# CycleOpsPro300toANTPlus_V2_0.net
KiCad netlist of a schematic drawn in EAGLE
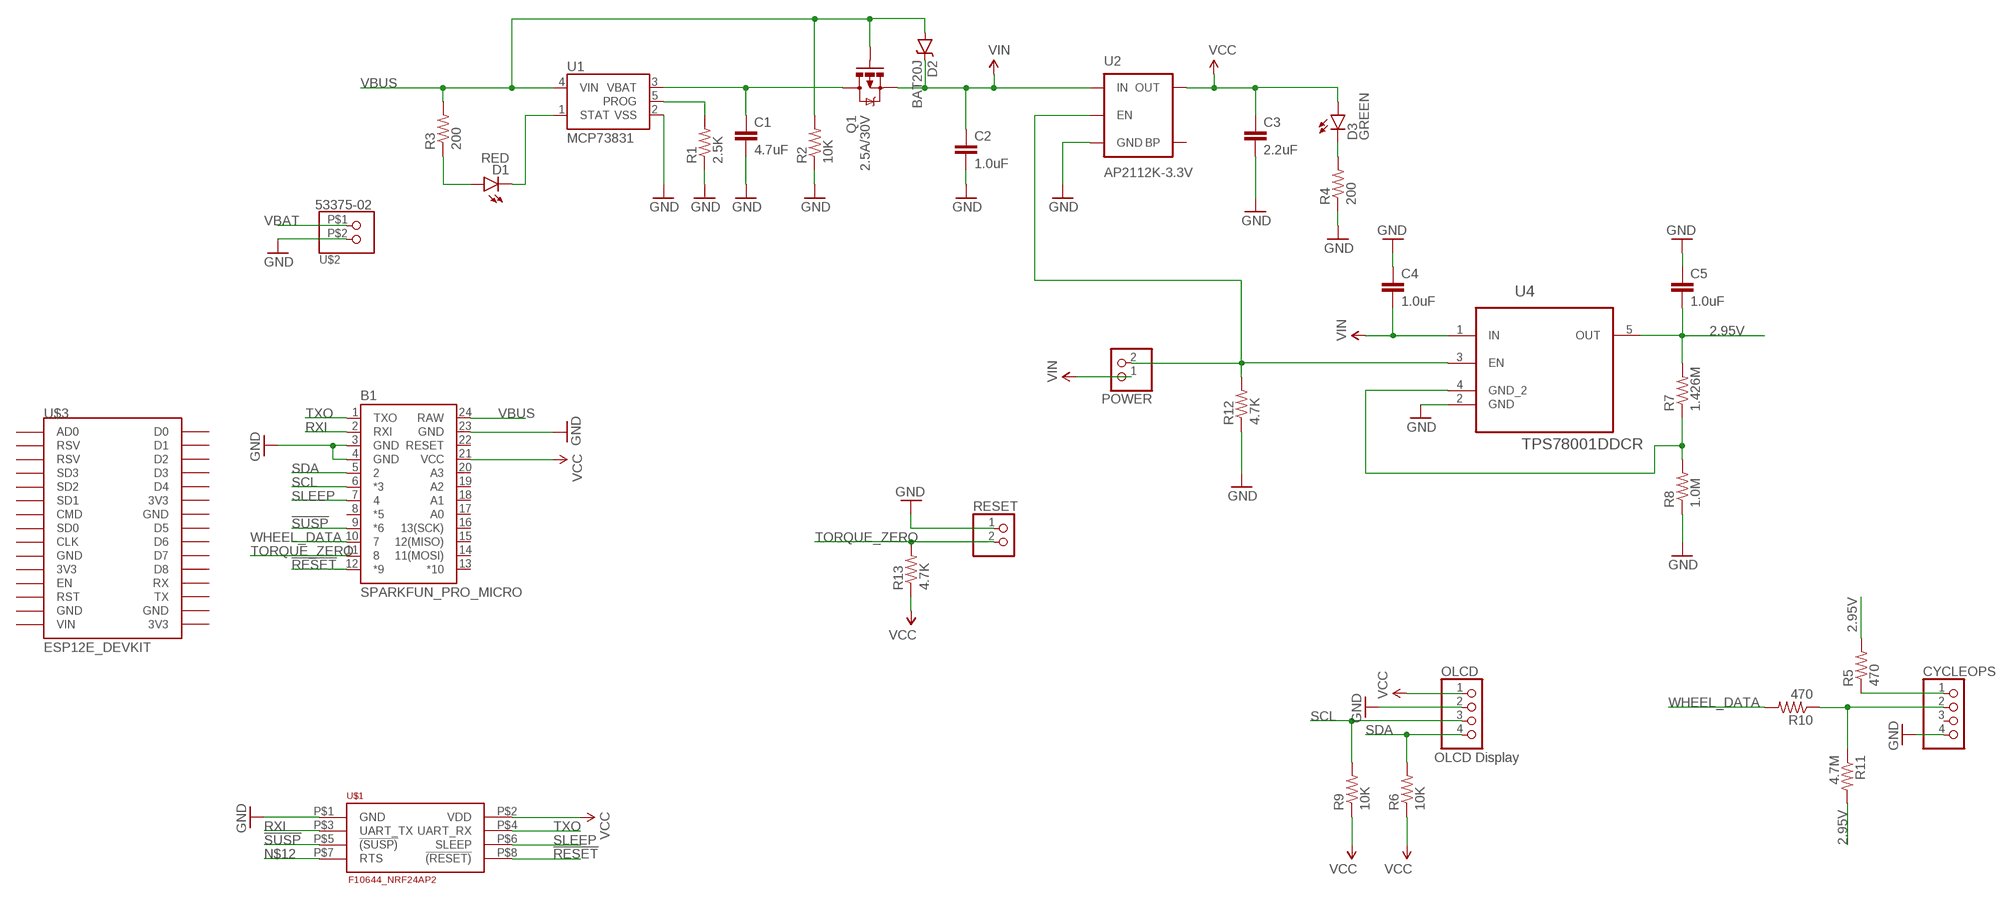
[diagram p0: schematic, sheet 1]

(export (version "E")
  (design (tool "Eeschema 10.0.6"))
  (components
    (comp (ref "B1")
      (value "SPARKFUN_PRO_MICRO")
      (footprint "eagle-import:SPARKFUN_PRO_MICRO")
      (libsource (lib "eagle-import") (part "SPARKFUN_PRO_MICRO"))
    )
    (comp (ref "C1")
      (value "4.7uF")
      (footprint "eagle-import:0603-CAP")
      (libsource (lib "eagle-import") (part "CAP0603-CAP"))
    )
    (comp (ref "C2")
      (value "1.0uF")
      (footprint "eagle-import:0603-CAP")
      (libsource (lib "eagle-import") (part "CAP0603-CAP"))
    )
    (comp (ref "C3")
      (value "2.2uF")
      (footprint "eagle-import:0603-CAP")
      (libsource (lib "eagle-import") (part "CAP0603-CAP"))
    )
    (comp (ref "C4")
      (value "1.0uF")
      (footprint "eagle-import:0603-CAP")
      (libsource (lib "eagle-import") (part "CAP0603-CAP"))
    )
    (comp (ref "C5")
      (value "1.0uF")
      (footprint "eagle-import:0603-CAP")
      (libsource (lib "eagle-import") (part "CAP0603-CAP"))
    )
    (comp (ref "CYCLEOPS")
      (value "PINHD-1X4")
      (footprint "eagle-import:1X04")
      (libsource (lib "eagle-import") (part "PINHD-1X4"))
    )
    (comp (ref "D1")
      (value "RED")
      (footprint "eagle-import:LED-0603")
      (libsource (lib "eagle-import") (part "LED0603"))
    )
    (comp (ref "D2")
      (value "BAT20J")
      (footprint "eagle-import:SOD-323")
      (libsource (lib "eagle-import") (part "DIODE-SCHOTTKY-BAT20J"))
    )
    (comp (ref "D3")
      (value "GREEN")
      (footprint "eagle-import:LED-0603")
      (libsource (lib "eagle-import") (part "LED0603"))
    )
    (comp (ref "OLCD")
      (value "PINHD-1X4")
      (footprint "eagle-import:1X04")
      (libsource (lib "eagle-import") (part "PINHD-1X4"))
    )
    (comp (ref "POWER")
      (value "PINHD-1X2")
      (footprint "eagle-import:1X02")
      (libsource (lib "eagle-import") (part "PINHD-1X2"))
    )
    (comp (ref "Q1")
      (value "2.5A/30V")
      (footprint "eagle-import:SOT23-3")
      (libsource (lib "eagle-import") (part "MOSFET-PCHANNELDMG2307L"))
    )
    (comp (ref "R1")
      (value "2.5K")
      (footprint "eagle-import:0603-RES")
      (libsource (lib "eagle-import") (part "RESISTOR0603-RES"))
    )
    (comp (ref "R2")
      (value "10K")
      (footprint "eagle-import:0603-RES")
      (libsource (lib "eagle-import") (part "RESISTOR0603-RES"))
    )
    (comp (ref "R3")
      (value "200")
      (footprint "eagle-import:0603-RES")
      (libsource (lib "eagle-import") (part "RESISTOR0603-RES"))
    )
    (comp (ref "R4")
      (value "200")
      (footprint "eagle-import:0603-RES")
      (libsource (lib "eagle-import") (part "RESISTOR0603-RES"))
    )
    (comp (ref "R5")
      (value "470")
      (footprint "eagle-import:0603-RES")
      (libsource (lib "eagle-import") (part "RESISTOR0603-RES"))
    )
    (comp (ref "R6")
      (value "10K")
      (footprint "eagle-import:0603-RES")
      (libsource (lib "eagle-import") (part "RESISTOR0603-RES"))
    )
    (comp (ref "R7")
      (value "1.426M")
      (footprint "eagle-import:0603-RES")
      (libsource (lib "eagle-import") (part "RESISTOR0603-RES"))
    )
    (comp (ref "R8")
      (value "1.0M")
      (footprint "eagle-import:0603-RES")
      (libsource (lib "eagle-import") (part "RESISTOR0603-RES"))
    )
    (comp (ref "R9")
      (value "10K")
      (footprint "eagle-import:0603-RES")
      (libsource (lib "eagle-import") (part "RESISTOR0603-RES"))
    )
    (comp (ref "R10")
      (value "470")
      (footprint "eagle-import:0603-RES")
      (libsource (lib "eagle-import") (part "RESISTOR0603-RES"))
    )
    (comp (ref "R11")
      (value "4.7M")
      (footprint "eagle-import:0603-RES")
      (libsource (lib "eagle-import") (part "RESISTOR0603-RES"))
    )
    (comp (ref "R12")
      (value "4.7K")
      (footprint "eagle-import:0603-RES")
      (libsource (lib "eagle-import") (part "RESISTOR0603-RES"))
    )
    (comp (ref "R13")
      (value "4.7K")
      (footprint "eagle-import:0603-RES")
      (libsource (lib "eagle-import") (part "RESISTOR0603-RES"))
    )
    (comp (ref "RESET")
      (value "PINHD-1X2")
      (footprint "eagle-import:1X02")
      (libsource (lib "eagle-import") (part "PINHD-1X2"))
    )
    (comp (ref "U$1")
      (value "F10644_NRF24AP2")
      (footprint "eagle-import:F10644_NRF24AP2")
      (libsource (lib "eagle-import") (part "F10644_NRF24AP2"))
    )
    (comp (ref "U$2")
      (value "53375-02")
      (footprint "eagle-import:53375-02")
      (libsource (lib "eagle-import") (part "53375-02"))
    )
    (comp (ref "U$3")
      (value "ESP12E_DEVKIT")
      (footprint "eagle-import:ESP12E_DEVKIT")
      (libsource (lib "eagle-import") (part "ESP12E_DEVKIT"))
    )
    (comp (ref "U1")
      (value "MCP73831")
      (footprint "eagle-import:SOT23-5")
      (libsource (lib "eagle-import") (part "MCP73831"))
    )
    (comp (ref "U2")
      (value "AP2112K-3.3V")
      (footprint "eagle-import:SOT23-5")
      (libsource (lib "eagle-import") (part "V_REG_LDOSMD"))
    )
    (comp (ref "U4")
      (value "TPS78001DDCR")
      (footprint "eagle-import:SOT95P280X110-5N")
      (fields (field (name "MPN") "TPS78223DDCR"))
      (libsource (lib "eagle-import") (part "TPS78223DDCR"))
    )
  )
  (nets
    (net (code "1") (name "/2.95V") (class "Default")
      (node (ref "C5") (pin "2") (pinfunction "2_2") (pintype "passive"))
      (node (ref "R11") (pin "2") (pinfunction "2_2") (pintype "passive"))
      (node (ref "R5") (pin "2") (pinfunction "2_2") (pintype "passive"))
      (node (ref "R7") (pin "2") (pinfunction "2_2") (pintype "passive"))
      (node (ref "U4") (pin "5") (pinfunction "OUT_5") (pintype "output"))
    )
    (net (code "2") (name "/N$12") (class "Default")
      (node (ref "U$1") (pin "P$7") (pinfunction "RTS_P$7") (pintype "bidirectional"))
    )
    (net (code "3") (name "/RXI") (class "Default")
      (node (ref "B1") (pin "2") (pinfunction "RXI_2") (pintype "bidirectional"))
      (node (ref "U$1") (pin "P$3") (pinfunction "UART_TX_P$3") (pintype "bidirectional"))
    )
    (net (code "4") (name "/SCL") (class "Default")
      (node (ref "B1") (pin "6") (pinfunction "*3_6") (pintype "bidirectional"))
      (node (ref "OLCD") (pin "3") (pinfunction "3_3") (pintype "passive"))
      (node (ref "R9") (pin "2") (pinfunction "2_2") (pintype "passive"))
    )
    (net (code "5") (name "/SDA") (class "Default")
      (node (ref "B1") (pin "5") (pinfunction "2_5") (pintype "bidirectional"))
      (node (ref "OLCD") (pin "4") (pinfunction "4_4") (pintype "passive"))
      (node (ref "R6") (pin "2") (pinfunction "2_2") (pintype "passive"))
    )
    (net (code "6") (name "/SLEEP") (class "Default")
      (node (ref "B1") (pin "7") (pinfunction "4_7") (pintype "bidirectional"))
      (node (ref "U$1") (pin "P$6") (pinfunction "SLEEP_P$6") (pintype "bidirectional"))
    )
    (net (code "7") (name "/TORQUE_ZERO") (class "Default")
      (node (ref "B1") (pin "11") (pinfunction "8_11") (pintype "bidirectional"))
      (node (ref "R13") (pin "2") (pinfunction "2_2") (pintype "passive"))
      (node (ref "RESET") (pin "2") (pinfunction "2_2") (pintype "passive"))
    )
    (net (code "8") (name "/TXO") (class "Default")
      (node (ref "B1") (pin "1") (pinfunction "TXO_1") (pintype "bidirectional"))
      (node (ref "U$1") (pin "P$4") (pinfunction "UART_RX_P$4") (pintype "bidirectional"))
    )
    (net (code "9") (name "/VBAT") (class "Default")
      (node (ref "C1") (pin "1") (pinfunction "1_1") (pintype "passive"))
      (node (ref "Q1") (pin "3") (pinfunction "D_3") (pintype "passive"))
      (node (ref "U$2") (pin "P$1") (pinfunction "P$1_P$1") (pintype "bidirectional"))
      (node (ref "U1") (pin "3") (pinfunction "VBAT_3") (pintype "power_in"))
    )
    (net (code "10") (name "/VBUS") (class "Default")
      (node (ref "B1") (pin "24") (pinfunction "RAW_24") (pintype "power_in"))
      (node (ref "D2") (pin "A") (pinfunction "A_A") (pintype "passive"))
      (node (ref "Q1") (pin "1") (pinfunction "G_1") (pintype "passive"))
      (node (ref "R2") (pin "2") (pinfunction "2_2") (pintype "passive"))
      (node (ref "R3") (pin "2") (pinfunction "2_2") (pintype "passive"))
      (node (ref "U1") (pin "4") (pinfunction "VIN_4") (pintype "power_in"))
    )
    (net (code "11") (name "/WHEEL_DATA") (class "Default")
      (node (ref "B1") (pin "10") (pinfunction "7_10") (pintype "bidirectional"))
      (node (ref "R10") (pin "2") (pinfunction "2_2") (pintype "passive"))
    )
    (net (code "12") (name "/~{RESET}") (class "Default")
      (node (ref "B1") (pin "12") (pinfunction "*9_12") (pintype "bidirectional"))
      (node (ref "U$1") (pin "P$8") (pinfunction "~{(RESET})_P$8") (pintype "bidirectional"))
    )
    (net (code "13") (name "/~{SUSP}") (class "Default")
      (node (ref "B1") (pin "9") (pinfunction "*6_9") (pintype "bidirectional"))
      (node (ref "U$1") (pin "P$5") (pinfunction "~{(SUSP})_P$5") (pintype "bidirectional"))
    )
    (net (code "14") (name "GND") (class "Default")
      (node (ref "B1") (pin "23") (pinfunction "GND_23") (pintype "power_in"))
      (node (ref "B1") (pin "3") (pinfunction "GND_3") (pintype "power_in"))
      (node (ref "B1") (pin "4") (pinfunction "GND_4") (pintype "power_in"))
      (node (ref "C1") (pin "2") (pinfunction "2_2") (pintype "passive"))
      (node (ref "C2") (pin "2") (pinfunction "2_2") (pintype "passive"))
      (node (ref "C3") (pin "2") (pinfunction "2_2") (pintype "passive"))
      (node (ref "C4") (pin "1") (pinfunction "1_1") (pintype "passive"))
      (node (ref "C5") (pin "1") (pinfunction "1_1") (pintype "passive"))
      (node (ref "CYCLEOPS") (pin "4") (pinfunction "4_4") (pintype "passive"))
      (node (ref "OLCD") (pin "2") (pinfunction "2_2") (pintype "passive"))
      (node (ref "R1") (pin "1") (pinfunction "1_1") (pintype "passive"))
      (node (ref "R12") (pin "1") (pinfunction "1_1") (pintype "passive"))
      (node (ref "R2") (pin "1") (pinfunction "1_1") (pintype "passive"))
      (node (ref "R4") (pin "1") (pinfunction "1_1") (pintype "passive"))
      (node (ref "R8") (pin "1") (pinfunction "1_1") (pintype "passive"))
      (node (ref "RESET") (pin "1") (pinfunction "1_1") (pintype "passive"))
      (node (ref "U$1") (pin "P$1") (pinfunction "GND_P$1") (pintype "bidirectional"))
      (node (ref "U$2") (pin "P$2") (pinfunction "P$2_P$2") (pintype "bidirectional"))
      (node (ref "U1") (pin "2") (pinfunction "VSS_2") (pintype "power_in"))
      (node (ref "U2") (pin "2") (pinfunction "GND_2") (pintype "input"))
      (node (ref "U4") (pin "2") (pinfunction "GND_2") (pintype "passive"))
    )
    (net (code "15") (name "Net-(CYCLEOPS-Pad1)") (class "Default")
      (node (ref "CYCLEOPS") (pin "1") (pinfunction "1_1") (pintype "passive"))
      (node (ref "R5") (pin "1") (pinfunction "1_1") (pintype "passive"))
    )
    (net (code "16") (name "Net-(CYCLEOPS-Pad2)") (class "Default")
      (node (ref "CYCLEOPS") (pin "2") (pinfunction "2_2") (pintype "passive"))
      (node (ref "R10") (pin "1") (pinfunction "1_1") (pintype "passive"))
      (node (ref "R11") (pin "1") (pinfunction "1_1") (pintype "passive"))
    )
    (net (code "17") (name "Net-(D1-PadA)") (class "Default")
      (node (ref "D1") (pin "A") (pinfunction "A_A") (pintype "passive"))
      (node (ref "R3") (pin "1") (pinfunction "1_1") (pintype "passive"))
    )
    (net (code "18") (name "Net-(D3-PadC)") (class "Default")
      (node (ref "D3") (pin "C") (pinfunction "C_C") (pintype "passive"))
      (node (ref "R4") (pin "2") (pinfunction "2_2") (pintype "passive"))
    )
    (net (code "19") (name "Net-(U1-PROG)") (class "Default")
      (node (ref "R1") (pin "2") (pinfunction "2_2") (pintype "passive"))
      (node (ref "U1") (pin "5") (pinfunction "PROG_5") (pintype "input"))
    )
    (net (code "20") (name "Net-(U1-STAT)") (class "Default")
      (node (ref "D1") (pin "C") (pinfunction "C_C") (pintype "passive"))
      (node (ref "U1") (pin "1") (pinfunction "STAT_1") (pintype "output"))
    )
    (net (code "21") (name "Net-(U2-EN)") (class "Default")
      (node (ref "POWER") (pin "2") (pinfunction "2_2") (pintype "passive"))
      (node (ref "R12") (pin "2") (pinfunction "2_2") (pintype "passive"))
      (node (ref "U2") (pin "3") (pinfunction "EN_3") (pintype "input"))
      (node (ref "U4") (pin "3") (pinfunction "EN_3") (pintype "input"))
    )
    (net (code "22") (name "Net-(U4-GND_2)") (class "Default")
      (node (ref "R7") (pin "1") (pinfunction "1_1") (pintype "passive"))
      (node (ref "R8") (pin "2") (pinfunction "2_2") (pintype "passive"))
      (node (ref "U4") (pin "4") (pinfunction "GND_2_4") (pintype "passive"))
    )
    (net (code "23") (name "VCC") (class "Default")
      (node (ref "B1") (pin "21") (pinfunction "VCC_21") (pintype "power_in"))
      (node (ref "C3") (pin "1") (pinfunction "1_1") (pintype "passive"))
      (node (ref "D3") (pin "A") (pinfunction "A_A") (pintype "passive"))
      (node (ref "OLCD") (pin "1") (pinfunction "1_1") (pintype "passive"))
      (node (ref "R13") (pin "1") (pinfunction "1_1") (pintype "passive"))
      (node (ref "R6") (pin "1") (pinfunction "1_1") (pintype "passive"))
      (node (ref "R9") (pin "1") (pinfunction "1_1") (pintype "passive"))
      (node (ref "U$1") (pin "P$2") (pinfunction "VDD_P$2") (pintype "bidirectional"))
      (node (ref "U2") (pin "5") (pinfunction "OUT_5") (pintype "passive"))
    )
    (net (code "24") (name "VIN") (class "Default")
      (node (ref "C2") (pin "1") (pinfunction "1_1") (pintype "passive"))
      (node (ref "C4") (pin "2") (pinfunction "2_2") (pintype "passive"))
      (node (ref "D2") (pin "C") (pinfunction "C_C") (pintype "passive"))
      (node (ref "POWER") (pin "1") (pinfunction "1_1") (pintype "passive"))
      (node (ref "Q1") (pin "2") (pinfunction "S_2") (pintype "passive"))
      (node (ref "U2") (pin "1") (pinfunction "IN_1") (pintype "input"))
      (node (ref "U4") (pin "1") (pinfunction "IN_1") (pintype "input"))
    )
    (net (code "25") (name "unconnected-(B1-*5-Pad8)") (class "Default")
      (node (ref "B1") (pin "8") (pinfunction "*5_8") (pintype "bidirectional"))
    )
    (net (code "26") (name "unconnected-(B1-*10-Pad13)") (class "Default")
      (node (ref "B1") (pin "13") (pinfunction "*10_13") (pintype "bidirectional"))
    )
    (net (code "27") (name "unconnected-(B1-11(MOSI)-Pad14)") (class "Default")
      (node (ref "B1") (pin "14") (pinfunction "11(MOSI)_14") (pintype "bidirectional"))
    )
    (net (code "28") (name "unconnected-(B1-12(MISO)-Pad15)") (class "Default")
      (node (ref "B1") (pin "15") (pinfunction "12(MISO)_15") (pintype "bidirectional"))
    )
    (net (code "29") (name "unconnected-(B1-13(SCK)-Pad16)") (class "Default")
      (node (ref "B1") (pin "16") (pinfunction "13(SCK)_16") (pintype "bidirectional"))
    )
    (net (code "30") (name "unconnected-(B1-A0-Pad17)") (class "Default")
      (node (ref "B1") (pin "17") (pinfunction "A0_17") (pintype "bidirectional"))
    )
    (net (code "31") (name "unconnected-(B1-A1-Pad18)") (class "Default")
      (node (ref "B1") (pin "18") (pinfunction "A1_18") (pintype "bidirectional"))
    )
    (net (code "32") (name "unconnected-(B1-A2-Pad19)") (class "Default")
      (node (ref "B1") (pin "19") (pinfunction "A2_19") (pintype "bidirectional"))
    )
    (net (code "33") (name "unconnected-(B1-A3-Pad20)") (class "Default")
      (node (ref "B1") (pin "20") (pinfunction "A3_20") (pintype "bidirectional"))
    )
    (net (code "34") (name "unconnected-(B1-RESET-Pad22)") (class "Default")
      (node (ref "B1") (pin "22") (pinfunction "RESET_22") (pintype "bidirectional"))
    )
    (net (code "35") (name "unconnected-(CYCLEOPS-Pad3)") (class "Default")
      (node (ref "CYCLEOPS") (pin "3") (pinfunction "3_3") (pintype "passive"))
    )
    (net (code "36") (name "unconnected-(U$3-3V3-Pad3V3@0)") (class "Default")
      (node (ref "U$3") (pin "3V3@0") (pinfunction "3V3_3V3@0") (pintype "bidirectional"))
    )
    (net (code "37") (name "unconnected-(U$3-3V3-Pad3V3@1)") (class "Default")
      (node (ref "U$3") (pin "3V3@1") (pinfunction "3V3_3V3@1") (pintype "bidirectional"))
    )
    (net (code "38") (name "unconnected-(U$3-3V3-Pad3V3@2)") (class "Default")
      (node (ref "U$3") (pin "3V3@2") (pinfunction "3V3_3V3@2") (pintype "bidirectional"))
    )
    (net (code "39") (name "unconnected-(U$3-GND-PadGND@0)") (class "Default")
      (node (ref "U$3") (pin "GND@0") (pinfunction "GND_GND@0") (pintype "bidirectional"))
    )
    (net (code "40") (name "unconnected-(U$3-GND-PadGND@1)") (class "Default")
      (node (ref "U$3") (pin "GND@1") (pinfunction "GND_GND@1") (pintype "bidirectional"))
    )
    (net (code "41") (name "unconnected-(U$3-GND-PadGND@2)") (class "Default")
      (node (ref "U$3") (pin "GND@2") (pinfunction "GND_GND@2") (pintype "bidirectional"))
    )
    (net (code "42") (name "unconnected-(U$3-GND-PadGND@3)") (class "Default")
      (node (ref "U$3") (pin "GND@3") (pinfunction "GND_GND@3") (pintype "bidirectional"))
    )
    (net (code "43") (name "unconnected-(U$3-PadAD0)") (class "Default")
      (node (ref "U$3") (pin "AD0") (pinfunction "AD0_AD0") (pintype "bidirectional"))
    )
    (net (code "44") (name "unconnected-(U$3-PadCLK)") (class "Default")
      (node (ref "U$3") (pin "CLK") (pinfunction "CLK_CLK") (pintype "bidirectional"))
    )
    (net (code "45") (name "unconnected-(U$3-PadCMD)") (class "Default")
      (node (ref "U$3") (pin "CMD") (pinfunction "CMD_CMD") (pintype "bidirectional"))
    )
    (net (code "46") (name "unconnected-(U$3-PadD0)") (class "Default")
      (node (ref "U$3") (pin "D0") (pinfunction "D0_D0") (pintype "bidirectional"))
    )
    (net (code "47") (name "unconnected-(U$3-PadD1)") (class "Default")
      (node (ref "U$3") (pin "D1") (pinfunction "D1_D1") (pintype "bidirectional"))
    )
    (net (code "48") (name "unconnected-(U$3-PadD2)") (class "Default")
      (node (ref "U$3") (pin "D2") (pinfunction "D2_D2") (pintype "bidirectional"))
    )
    (net (code "49") (name "unconnected-(U$3-PadD3)") (class "Default")
      (node (ref "U$3") (pin "D3") (pinfunction "D3_D3") (pintype "bidirectional"))
    )
    (net (code "50") (name "unconnected-(U$3-PadD4)") (class "Default")
      (node (ref "U$3") (pin "D4") (pinfunction "D4_D4") (pintype "bidirectional"))
    )
    (net (code "51") (name "unconnected-(U$3-PadD5)") (class "Default")
      (node (ref "U$3") (pin "D5") (pinfunction "D5_D5") (pintype "bidirectional"))
    )
    (net (code "52") (name "unconnected-(U$3-PadD6)") (class "Default")
      (node (ref "U$3") (pin "D6") (pinfunction "D6_D6") (pintype "bidirectional"))
    )
    (net (code "53") (name "unconnected-(U$3-PadD7)") (class "Default")
      (node (ref "U$3") (pin "D7") (pinfunction "D7_D7") (pintype "bidirectional"))
    )
    (net (code "54") (name "unconnected-(U$3-PadD8)") (class "Default")
      (node (ref "U$3") (pin "D8") (pinfunction "D8_D8") (pintype "bidirectional"))
    )
    (net (code "55") (name "unconnected-(U$3-PadEN)") (class "Default")
      (node (ref "U$3") (pin "EN") (pinfunction "EN_EN") (pintype "bidirectional"))
    )
    (net (code "56") (name "unconnected-(U$3-PadRST)") (class "Default")
      (node (ref "U$3") (pin "RST") (pinfunction "RST_RST") (pintype "bidirectional"))
    )
    (net (code "57") (name "unconnected-(U$3-PadRX)") (class "Default")
      (node (ref "U$3") (pin "RX") (pinfunction "RX_RX") (pintype "bidirectional"))
    )
    (net (code "58") (name "unconnected-(U$3-PadSD0)") (class "Default")
      (node (ref "U$3") (pin "SD0") (pinfunction "SD0_SD0") (pintype "bidirectional"))
    )
    (net (code "59") (name "unconnected-(U$3-PadSD1)") (class "Default")
      (node (ref "U$3") (pin "SD1") (pinfunction "SD1_SD1") (pintype "bidirectional"))
    )
    (net (code "60") (name "unconnected-(U$3-PadSD2)") (class "Default")
      (node (ref "U$3") (pin "SD2") (pinfunction "SD2_SD2") (pintype "bidirectional"))
    )
    (net (code "61") (name "unconnected-(U$3-PadSD3)") (class "Default")
      (node (ref "U$3") (pin "SD3") (pinfunction "SD3_SD3") (pintype "bidirectional"))
    )
    (net (code "62") (name "unconnected-(U$3-PadTX)") (class "Default")
      (node (ref "U$3") (pin "TX") (pinfunction "TX_TX") (pintype "bidirectional"))
    )
    (net (code "63") (name "unconnected-(U$3-PadVIN)") (class "Default")
      (node (ref "U$3") (pin "VIN") (pinfunction "VIN_VIN") (pintype "bidirectional"))
    )
    (net (code "64") (name "unconnected-(U$3-RSV-PadRSV@0)") (class "Default")
      (node (ref "U$3") (pin "RSV@0") (pinfunction "RSV_RSV@0") (pintype "bidirectional"))
    )
    (net (code "65") (name "unconnected-(U$3-RSV-PadRSV@1)") (class "Default")
      (node (ref "U$3") (pin "RSV@1") (pinfunction "RSV_RSV@1") (pintype "bidirectional"))
    )
    (net (code "66") (name "unconnected-(U2-BP-Pad4)") (class "Default")
      (node (ref "U2") (pin "4") (pinfunction "BP_4") (pintype "input"))
    )
  )
)
